# Analog_Hall.net
KiCad netlist of a schematic drawn in Altium Designer
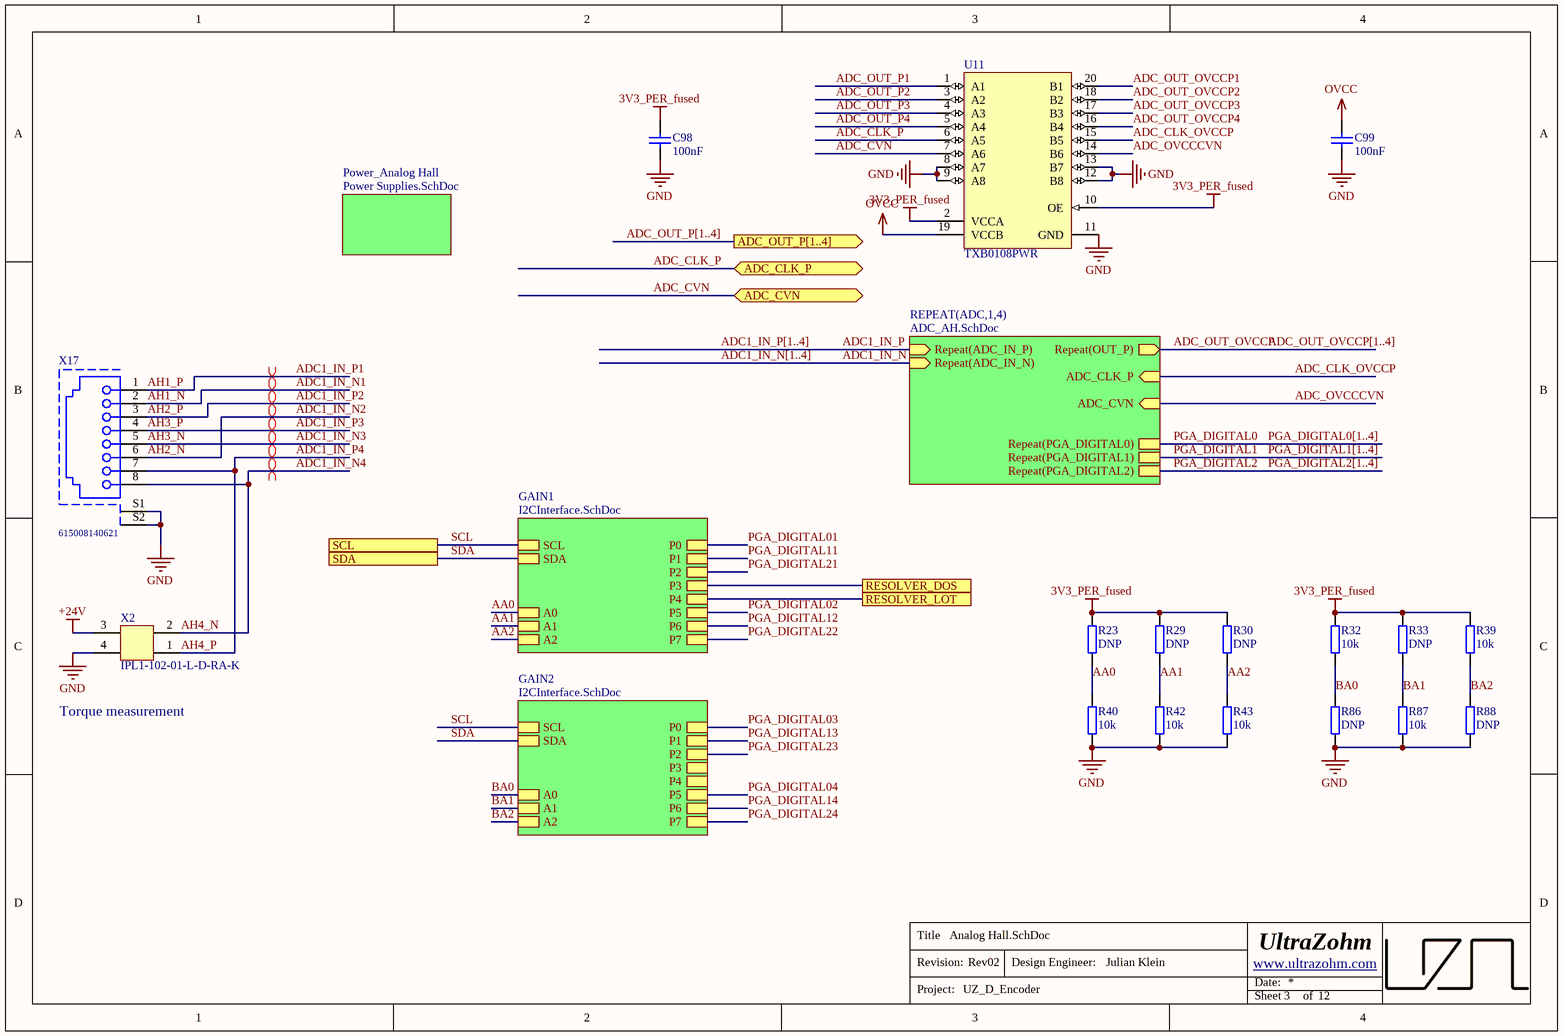
[diagram p0: Analog Hall.SchDoc]

(export (version "E")
  (design (tool "Eeschema 10.0.6"))
  (components
    (comp (ref "C98")
      (value "100nF")
      (footprint "CAPC1608X07N")
      (fields (field (name "MF") "Würth") (field (name "MPN") "885012206071") (field (name "VOLTAGE") "25V"))
      (libsource (lib "UltraZohm_ADC") (part "Cap_0603"))
    )
    (comp (ref "C99")
      (value "100nF")
      (footprint "CAPC1608X07N")
      (fields (field (name "MF") "Würth") (field (name "MPN") "885012206071") (field (name "VOLTAGE") "16V"))
      (libsource (lib "UltraZohm_ADC") (part "Cap_0603"))
    )
    (comp (ref "R23")
      (value "DNP")
      (footprint "RESC1608X06N")
      (fields (field (name "MF") "Vishay") (field (name "MPN") "CRCW06030000Z0EAC"))
      (libsource (lib "UltraZohm_ADC") (part "R_0603"))
    )
    (comp (ref "R29")
      (value "DNP")
      (footprint "RESC1608X06N")
      (fields (field (name "MF") "Vishay") (field (name "MPN") "CRCW06030000Z0EAC"))
      (libsource (lib "UltraZohm_ADC") (part "R_0603"))
    )
    (comp (ref "R30")
      (value "DNP")
      (footprint "RESC1608X06N")
      (fields (field (name "MF") "Vishay") (field (name "MPN") "CRCW06030000Z0EAC"))
      (libsource (lib "UltraZohm_ADC") (part "R_0603"))
    )
    (comp (ref "R32")
      (value "10k")
      (footprint "RESC1608X06N")
      (fields (field (name "MF") "Vishay") (field (name "MPN") "CRCW06030000Z0EAC"))
      (libsource (lib "UltraZohm_ADC") (part "R_0603"))
    )
    (comp (ref "R33")
      (value "DNP")
      (footprint "RESC1608X06N")
      (fields (field (name "MF") "Vishay") (field (name "MPN") "CRCW06030000Z0EAC"))
      (libsource (lib "UltraZohm_ADC") (part "R_0603"))
    )
    (comp (ref "R39")
      (value "10k")
      (footprint "RESC1608X06N")
      (fields (field (name "MF") "Vishay") (field (name "MPN") "CRCW06030000Z0EAC"))
      (libsource (lib "UltraZohm_ADC") (part "R_0603"))
    )
    (comp (ref "R40")
      (value "10k")
      (footprint "RESC1608X06N")
      (fields (field (name "MF") "Vishay") (field (name "MPN") "CRCW06030000Z0EAC"))
      (libsource (lib "UltraZohm_ADC") (part "R_0603"))
    )
    (comp (ref "R42")
      (value "10k")
      (footprint "RESC1608X06N")
      (fields (field (name "MF") "Vishay") (field (name "MPN") "CRCW06030000Z0EAC"))
      (libsource (lib "UltraZohm_ADC") (part "R_0603"))
    )
    (comp (ref "R43")
      (value "10k")
      (footprint "RESC1608X06N")
      (fields (field (name "MF") "Vishay") (field (name "MPN") "CRCW06030000Z0EAC"))
      (libsource (lib "UltraZohm_ADC") (part "R_0603"))
    )
    (comp (ref "R86")
      (value "DNP")
      (footprint "RESC1608X06N")
      (fields (field (name "MF") "Vishay") (field (name "MPN") "CRCW06030000Z0EAC"))
      (libsource (lib "UltraZohm_ADC") (part "R_0603"))
    )
    (comp (ref "R87")
      (value "10k")
      (footprint "RESC1608X06N")
      (fields (field (name "MF") "Vishay") (field (name "MPN") "CRCW06030000Z0EAC"))
      (libsource (lib "UltraZohm_ADC") (part "R_0603"))
    )
    (comp (ref "R88")
      (value "DNP")
      (footprint "RESC1608X06N")
      (fields (field (name "MF") "Vishay") (field (name "MPN") "CRCW06030000Z0EAC"))
      (libsource (lib "UltraZohm_ADC") (part "R_0603"))
    )
    (comp (ref "U11")
      (value "TXB0108PWR")
      (footprint "PW0020A_L")
      (fields (field (name "MANUFACTURER") "Texas Instruments"))
      (libsource (lib "Altium Content Vault") (part "TI-TXB0108-PW-20"))
    )
    (comp (ref "X2")
      (value "IPL1-102-01-L-D-RA-K")
      (footprint "Conector 2x2 TH Horizontal")
      (description "CONN HEADER R/A 4 POS 2.54MM Through Hole")
      (fields (field (name "MF") "Samtec"))
      (libsource (lib "Componentes_SOC") (part "Conector 2x2 Horizontal"))
    )
    (comp (ref "X17")
      (value "615008140621")
      (footprint "615008140621")
      (description "Modular Jack WR-MJ, Tab Up, Shielded, with EMI Panel Finger, Horizontal Entry, THT, 8P8C")
      (fields (field (name "MF") "Wurth Elektronik") (field (name "PUBLISHER") "WurthElektronik"))
      (libsource (lib "Componentes_SOC") (part "615008140621"))
    )
  )
  (nets
    (net (code "1") (name "+24V") (class "Default") (node (ref "X2") (pin "3") (pintype "passive")))
    (net (code "2") (name "/AA0") (class "Default")
      (node (ref "R23") (pin "1") (pintype "passive"))
      (node (ref "R40") (pin "2") (pintype "passive"))
    )
    (net (code "3") (name "/AA1") (class "Default")
      (node (ref "R29") (pin "1") (pintype "passive"))
      (node (ref "R42") (pin "2") (pintype "passive"))
    )
    (net (code "4") (name "/AA2") (class "Default")
      (node (ref "R30") (pin "1") (pintype "passive"))
      (node (ref "R43") (pin "2") (pintype "passive"))
    )
    (net (code "6") (name "/ADC1_IN_N1") (class "Default")
      (node (ref "X17") (pin "2") (pinfunction "2_2") (pintype "passive"))
    )
    (net (code "7") (name "/ADC1_IN_N2") (class "Default")
      (node (ref "X17") (pin "6") (pinfunction "6_6") (pintype "passive"))
    )
    (net (code "8") (name "/ADC1_IN_N3") (class "Default")
      (node (ref "X17") (pin "5") (pinfunction "5_5") (pintype "passive"))
    )
    (net (code "9") (name "/ADC1_IN_N4") (class "Default")
      (node (ref "X17") (pin "8") (pinfunction "8_8") (pintype "passive"))
      (node (ref "X2") (pin "2") (pintype "passive"))
    )
    (net (code "12") (name "/ADC1_IN_P1") (class "Default")
      (node (ref "X17") (pin "1") (pinfunction "1_1") (pintype "passive"))
    )
    (net (code "13") (name "/ADC1_IN_P2") (class "Default")
      (node (ref "X17") (pin "3") (pinfunction "3_3") (pintype "passive"))
    )
    (net (code "14") (name "/ADC1_IN_P3") (class "Default")
      (node (ref "X17") (pin "4") (pinfunction "4_4") (pintype "passive"))
    )
    (net (code "15") (name "/ADC1_IN_P4") (class "Default")
      (node (ref "X17") (pin "7") (pinfunction "7_7") (pintype "passive"))
      (node (ref "X2") (pin "1") (pintype "passive"))
    )
    (net (code "17") (name "/ADC_CLK_OVCCP") (class "Default")
      (node (ref "U11") (pin "15") (pinfunction "B5_15") (pintype "bidirectional"))
    )
    (net (code "18") (name "/ADC_CLK_P") (class "Default")
      (node (ref "U11") (pin "6") (pinfunction "A5_6") (pintype "bidirectional"))
    )
    (net (code "19") (name "/ADC_CVN") (class "Default")
      (node (ref "U11") (pin "7") (pinfunction "A6_7") (pintype "bidirectional"))
    )
    (net (code "21") (name "/ADC_OUT_OVCCP1") (class "Default")
      (node (ref "U11") (pin "20") (pinfunction "B1_20") (pintype "bidirectional"))
    )
    (net (code "22") (name "/ADC_OUT_OVCCP2") (class "Default")
      (node (ref "U11") (pin "18") (pinfunction "B2_18") (pintype "bidirectional"))
    )
    (net (code "23") (name "/ADC_OUT_OVCCP3") (class "Default")
      (node (ref "U11") (pin "17") (pinfunction "B3_17") (pintype "bidirectional"))
    )
    (net (code "24") (name "/ADC_OUT_OVCCP4") (class "Default")
      (node (ref "U11") (pin "16") (pinfunction "B4_16") (pintype "bidirectional"))
    )
    (net (code "26") (name "/ADC_OUT_P1") (class "Default")
      (node (ref "U11") (pin "1") (pinfunction "A1_1") (pintype "bidirectional"))
    )
    (net (code "27") (name "/ADC_OUT_P2") (class "Default")
      (node (ref "U11") (pin "3") (pinfunction "A2_3") (pintype "bidirectional"))
    )
    (net (code "28") (name "/ADC_OUT_P3") (class "Default")
      (node (ref "U11") (pin "4") (pinfunction "A3_4") (pintype "bidirectional"))
    )
    (net (code "29") (name "/ADC_OUT_P4") (class "Default")
      (node (ref "U11") (pin "5") (pinfunction "A4_5") (pintype "bidirectional"))
    )
    (net (code "31") (name "/ADC_OVCCCVN") (class "Default")
      (node (ref "U11") (pin "14") (pinfunction "B6_14") (pintype "bidirectional"))
    )
    (net (code "32") (name "/BA0") (class "Default")
      (node (ref "R32") (pin "2") (pintype "passive"))
      (node (ref "R86") (pin "1") (pintype "passive"))
    )
    (net (code "33") (name "/BA1") (class "Default")
      (node (ref "R33") (pin "2") (pintype "passive"))
      (node (ref "R87") (pin "1") (pintype "passive"))
    )
    (net (code "34") (name "/BA2") (class "Default")
      (node (ref "R39") (pin "2") (pintype "passive"))
      (node (ref "R88") (pin "1") (pintype "passive"))
    )
    (net (code "59") (name "3V3_PER_fused") (class "Default")
      (node (ref "C98") (pin "1") (pinfunction "1_1") (pintype "passive"))
      (node (ref "R23") (pin "2") (pintype "passive"))
      (node (ref "R29") (pin "2") (pintype "passive"))
      (node (ref "R30") (pin "2") (pintype "passive"))
      (node (ref "R32") (pin "1") (pintype "passive"))
      (node (ref "R33") (pin "1") (pintype "passive"))
      (node (ref "R39") (pin "1") (pintype "passive"))
      (node (ref "U11") (pin "10") (pinfunction "OE_10") (pintype "input"))
      (node (ref "U11") (pin "2") (pinfunction "VCCA_2") (pintype "power_in"))
    )
    (net (code "60") (name "GND") (class "Default")
      (node (ref "C98") (pin "2") (pinfunction "2_2") (pintype "passive"))
      (node (ref "C99") (pin "2") (pinfunction "2_2") (pintype "passive"))
      (node (ref "R40") (pin "1") (pintype "passive"))
      (node (ref "R42") (pin "1") (pintype "passive"))
      (node (ref "R43") (pin "1") (pintype "passive"))
      (node (ref "R86") (pin "2") (pintype "passive"))
      (node (ref "R87") (pin "2") (pintype "passive"))
      (node (ref "R88") (pin "2") (pintype "passive"))
      (node (ref "U11") (pin "11") (pinfunction "GND_11") (pintype "power_in"))
      (node (ref "U11") (pin "12") (pinfunction "B8_12") (pintype "bidirectional"))
      (node (ref "U11") (pin "13") (pinfunction "B7_13") (pintype "bidirectional"))
      (node (ref "U11") (pin "8") (pinfunction "A7_8") (pintype "bidirectional"))
      (node (ref "U11") (pin "9") (pinfunction "A8_9") (pintype "bidirectional"))
      (node (ref "X17") (pin "S1") (pinfunction "S1_S1") (pintype "passive"))
      (node (ref "X17") (pin "S2") (pinfunction "S2_S2") (pintype "passive"))
      (node (ref "X2") (pin "4") (pintype "passive"))
    )
    (net (code "61") (name "OVCC") (class "Default")
      (node (ref "C99") (pin "1") (pinfunction "1_1") (pintype "passive"))
      (node (ref "U11") (pin "19") (pinfunction "VCCB_19") (pintype "power_in"))
    )
  )
)
